# icm.net
KiCad netlist of a schematic drawn in Altium Designer
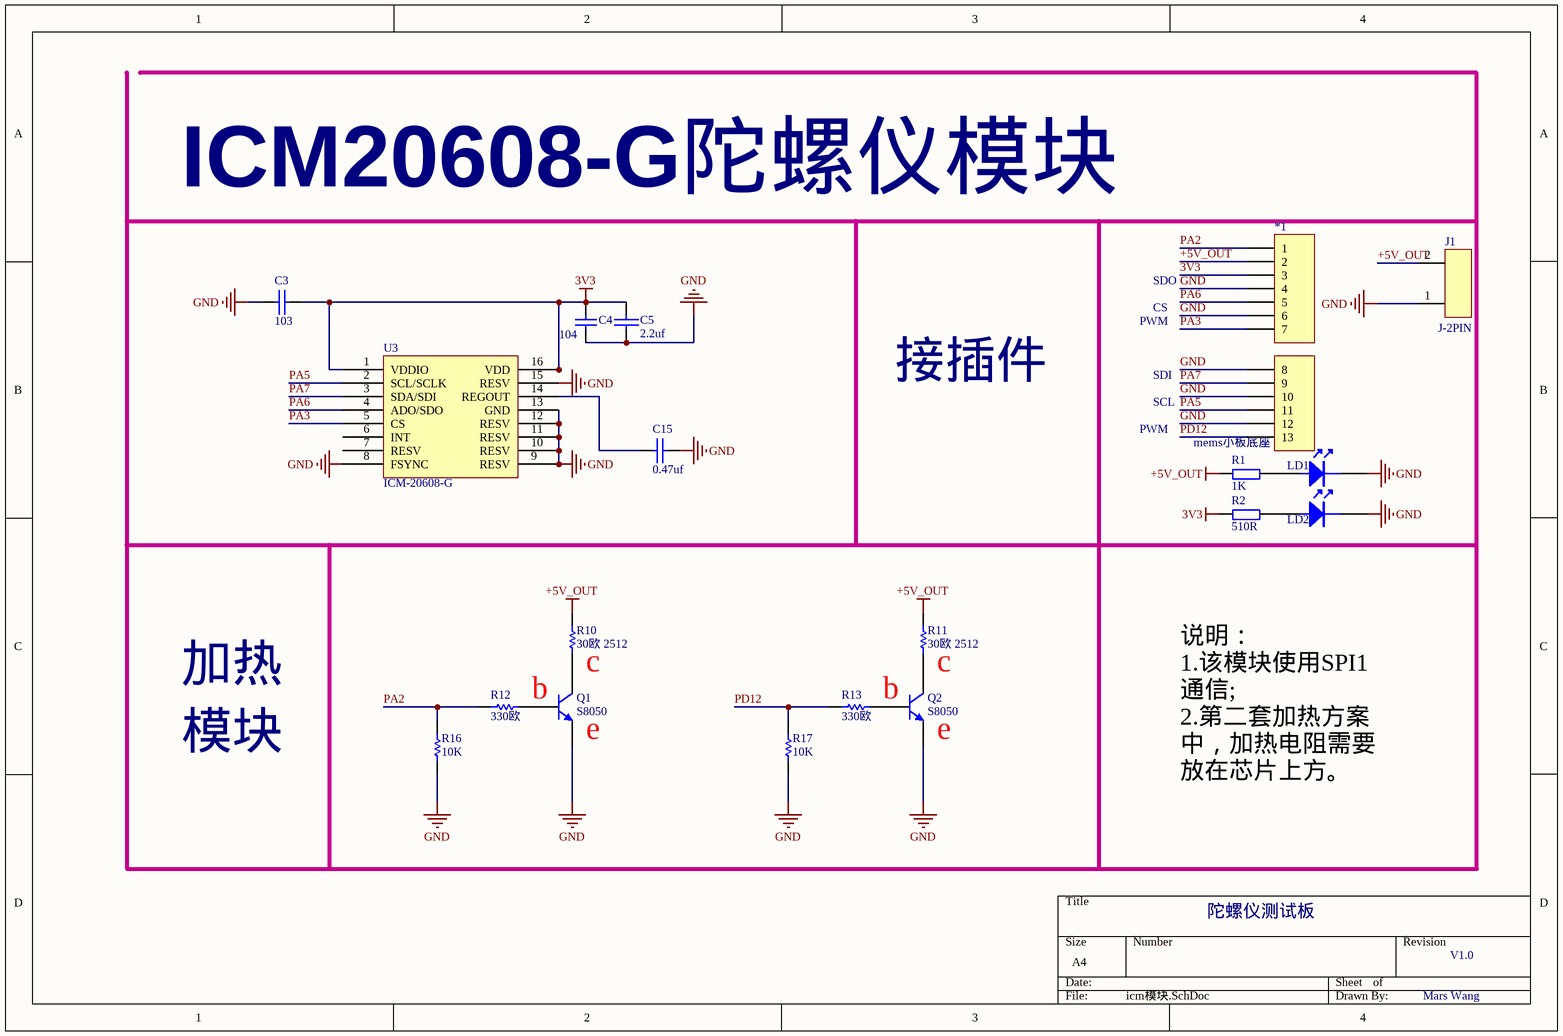
[diagram p0: icm模块.SchDoc]

(export (version "E")
  (design (tool "Eeschema 10.0.6"))
  (components
    (comp (ref "*1") (value "mems小板底座") (footprint "mems小板底座") (libsource (lib "ICM模块") (part "mems小板底座")))
    (comp (ref "C3")
      (value "103")
      (footprint "C-0805C")
      (description "Capacitor")
      (libsource (lib "ACTION原理图库") (part "C-贴片电容"))
    )
    (comp (ref "C4")
      (value "104")
      (footprint "C-0805C")
      (description "Capacitor")
      (fields (field (name "PUBLISHER") "Altium Limited"))
      (libsource (lib "Miscellaneous Devices") (part "C-贴片电容"))
    )
    (comp (ref "C5")
      (value "2.2uf")
      (footprint "C-0805C")
      (description "Capacitor")
      (libsource (lib "ACTION原理图库") (part "C-贴片电容"))
    )
    (comp (ref "C15")
      (value "0.47uf")
      (footprint "C-0805C")
      (description "Capacitor")
      (libsource (lib "ACTION原理图库") (part "C-贴片电容"))
    )
    (comp (ref "J1")
      (value "J-2PIN")
      (footprint "J-2-2.54-xh")
      (description "SOCKET")
      (libsource (lib "ACTION原理图库") (part "J-2PIN"))
    )
    (comp (ref "LD1") (value "~") (footprint "D-0603D") (libsource (lib "ACTION原理图库") (part "LED")))
    (comp (ref "LD2") (value "~") (footprint "D-0603D") (libsource (lib "ACTION原理图库") (part "LED")))
    (comp (ref "Q1")
      (value "S8050")
      (footprint "SOT-233-3")
      (description "NPN Bipolar Transistor")
      (fields (field (name "PUBLISHER") "Altium Limited"))
      (libsource (lib "Miscellaneous Devices") (part "NPN"))
    )
    (comp (ref "Q2")
      (value "S8050")
      (footprint "SOT-233-3")
      (description "NPN Bipolar Transistor")
      (fields (field (name "PUBLISHER") "Altium Limited"))
      (libsource (lib "Miscellaneous Devices") (part "NPN"))
    )
    (comp (ref "R1")
      (value "1K")
      (footprint "R-0603R")
      (description "RES, 10K, 5%, 0.1 W, 0603")
      (libsource (lib "ACTION原理图库") (part "Resistor"))
    )
    (comp (ref "R2")
      (value "510R")
      (footprint "R-0603R")
      (description "RES, 10K, 5%, 0.1 W, 0603")
      (libsource (lib "ACTION原理图库") (part "Resistor"))
    )
    (comp (ref "R10")
      (value "30欧 2512")
      (footprint "R-3925R（锰铜）")
      (description "Semiconductor Resistor")
      (fields (field (name "PUBLISHER") "Altium Limited"))
      (libsource (lib "大赛无线手柄") (part "Res Semi"))
    )
    (comp (ref "R11")
      (value "30欧 2512")
      (footprint "PCBComponent_1")
      (description "Semiconductor Resistor")
      (fields (field (name "PUBLISHER") "Altium Limited"))
      (libsource (lib "大赛无线手柄") (part "Res Semi"))
    )
    (comp (ref "R12")
      (value "330欧")
      (footprint "R-0603R")
      (description "Semiconductor Resistor")
      (fields (field (name "PUBLISHER") "Altium Limited"))
      (libsource (lib "altium-import") (part "root_0_Res Semi_"))
    )
    (comp (ref "R13")
      (value "330欧")
      (footprint "R-0603R")
      (description "Semiconductor Resistor")
      (fields (field (name "PUBLISHER") "Altium Limited"))
      (libsource (lib "altium-import") (part "root_0_Res Semi_"))
    )
    (comp (ref "R16")
      (value "10K")
      (footprint "R-0603R")
      (description "Semiconductor Resistor")
      (fields (field (name "PUBLISHER") "Altium Limited"))
      (libsource (lib "大赛无线手柄") (part "Res Semi"))
    )
    (comp (ref "R17")
      (value "10K")
      (footprint "R-0603R")
      (description "Semiconductor Resistor")
      (fields (field (name "PUBLISHER") "Altium Limited"))
      (libsource (lib "大赛无线手柄") (part "Res Semi"))
    )
    (comp (ref "U3")
      (value "ICM-20608-G")
      (footprint "ICM20608-G")
      (libsource (lib "ACTION原理图库") (part "ICM-20608-G"))
    )
  )
  (nets
    (net (code "1") (name "+5V_OUT") (class "Default")
      (node (ref "*1") (pin "2") (pinfunction "2_2") (pintype "passive"))
      (node (ref "J1") (pin "2") (pinfunction "2_2") (pintype "passive"))
      (node (ref "R1") (pin "1") (pintype "passive"))
      (node (ref "R10") (pin "2") (pinfunction "2_2") (pintype "passive"))
      (node (ref "R11") (pin "2") (pinfunction "2_2") (pintype "passive"))
    )
    (net (code "2") (name "/PA2") (class "Default")
      (node (ref "*1") (pin "1") (pinfunction "1_1") (pintype "passive"))
      (node (ref "R12") (pin "1") (pinfunction "1_1") (pintype "passive"))
      (node (ref "R16") (pin "2") (pinfunction "2_2") (pintype "passive"))
    )
    (net (code "3") (name "/PA3") (class "Default")
      (node (ref "*1") (pin "7") (pinfunction "7_7") (pintype "passive"))
      (node (ref "U3") (pin "5") (pinfunction "CS_5") (pintype "passive"))
    )
    (net (code "4") (name "/PA5") (class "Default")
      (node (ref "*1") (pin "11") (pinfunction "11_11") (pintype "passive"))
      (node (ref "U3") (pin "2") (pinfunction "SCL/SCLK_2") (pintype "passive"))
    )
    (net (code "5") (name "/PA6") (class "Default")
      (node (ref "*1") (pin "5") (pinfunction "5_5") (pintype "passive"))
      (node (ref "U3") (pin "4") (pinfunction "ADO/SDO_4") (pintype "passive"))
    )
    (net (code "6") (name "/PA7") (class "Default")
      (node (ref "*1") (pin "9") (pinfunction "9_9") (pintype "passive"))
      (node (ref "U3") (pin "3") (pinfunction "SDA/SDI_3") (pintype "passive"))
    )
    (net (code "7") (name "/PD12") (class "Default")
      (node (ref "*1") (pin "13") (pinfunction "13_13") (pintype "passive"))
      (node (ref "R13") (pin "1") (pinfunction "1_1") (pintype "passive"))
      (node (ref "R17") (pin "2") (pinfunction "2_2") (pintype "passive"))
    )
    (net (code "8") (name "3V3") (class "Default")
      (node (ref "*1") (pin "3") (pinfunction "3_3") (pintype "passive"))
      (node (ref "C3") (pin "1") (pinfunction "1_1") (pintype "passive"))
      (node (ref "C4") (pin "1") (pinfunction "1_1") (pintype "passive"))
      (node (ref "C5") (pin "2") (pinfunction "2_2") (pintype "passive"))
      (node (ref "R2") (pin "1") (pintype "passive"))
      (node (ref "U3") (pin "1") (pinfunction "VDDIO_1") (pintype "passive"))
      (node (ref "U3") (pin "16") (pinfunction "VDD_16") (pintype "passive"))
    )
    (net (code "9") (name "GND") (class "Default")
      (node (ref "*1") (pin "10") (pinfunction "10_10") (pintype "passive"))
      (node (ref "*1") (pin "12") (pinfunction "12_12") (pintype "passive"))
      (node (ref "*1") (pin "4") (pinfunction "4_4") (pintype "passive"))
      (node (ref "*1") (pin "6") (pinfunction "6_6") (pintype "passive"))
      (node (ref "*1") (pin "8") (pinfunction "8_8") (pintype "passive"))
      (node (ref "C15") (pin "1") (pinfunction "1_1") (pintype "passive"))
      (node (ref "C3") (pin "2") (pinfunction "2_2") (pintype "passive"))
      (node (ref "C4") (pin "2") (pinfunction "2_2") (pintype "passive"))
      (node (ref "C5") (pin "1") (pinfunction "1_1") (pintype "passive"))
      (node (ref "J1") (pin "1") (pinfunction "1_1") (pintype "passive"))
      (node (ref "LD1") (pin "2") (pinfunction "2_2") (pintype "passive"))
      (node (ref "LD2") (pin "2") (pinfunction "2_2") (pintype "passive"))
      (node (ref "Q1") (pin "3") (pinfunction "E_3") (pintype "passive"))
      (node (ref "Q2") (pin "3") (pinfunction "E_3") (pintype "passive"))
      (node (ref "R16") (pin "1") (pinfunction "1_1") (pintype "passive"))
      (node (ref "R17") (pin "1") (pinfunction "1_1") (pintype "passive"))
      (node (ref "U3") (pin "10") (pinfunction "RESV_10") (pintype "passive"))
      (node (ref "U3") (pin "11") (pinfunction "RESV_11") (pintype "passive"))
      (node (ref "U3") (pin "12") (pinfunction "RESV_12") (pintype "passive"))
      (node (ref "U3") (pin "13") (pinfunction "GND_13") (pintype "passive"))
      (node (ref "U3") (pin "15") (pinfunction "RESV_15") (pintype "passive"))
      (node (ref "U3") (pin "8") (pinfunction "FSYNC_8") (pintype "passive"))
      (node (ref "U3") (pin "9") (pinfunction "RESV_9") (pintype "passive"))
    )
    (net (code "10") (name "Net-(LD1-Pad1)") (class "Default")
      (node (ref "LD1") (pin "1") (pinfunction "1_1") (pintype "passive"))
      (node (ref "R1") (pin "2") (pintype "passive"))
    )
    (net (code "11") (name "Net-(LD2-Pad1)") (class "Default")
      (node (ref "LD2") (pin "1") (pinfunction "1_1") (pintype "passive"))
      (node (ref "R2") (pin "2") (pintype "passive"))
    )
    (net (code "12") (name "Net-(Q1-B)") (class "Default")
      (node (ref "Q1") (pin "2") (pinfunction "B_2") (pintype "passive"))
      (node (ref "R12") (pin "2") (pinfunction "2_2") (pintype "passive"))
    )
    (net (code "13") (name "Net-(Q1-C)") (class "Default")
      (node (ref "Q1") (pin "1") (pinfunction "C_1") (pintype "passive"))
      (node (ref "R10") (pin "1") (pinfunction "1_1") (pintype "passive"))
    )
    (net (code "14") (name "Net-(Q2-B)") (class "Default")
      (node (ref "Q2") (pin "2") (pinfunction "B_2") (pintype "passive"))
      (node (ref "R13") (pin "2") (pinfunction "2_2") (pintype "passive"))
    )
    (net (code "15") (name "Net-(Q2-C)") (class "Default")
      (node (ref "Q2") (pin "1") (pinfunction "C_1") (pintype "passive"))
      (node (ref "R11") (pin "1") (pinfunction "1_1") (pintype "passive"))
    )
    (net (code "16") (name "Net-(U3-REGOUT)") (class "Default")
      (node (ref "C15") (pin "2") (pinfunction "2_2") (pintype "passive"))
      (node (ref "U3") (pin "14") (pinfunction "REGOUT_14") (pintype "passive"))
    )
    (net (code "17") (name "unconnected-(U3-INT-Pad6)") (class "Default")
      (node (ref "U3") (pin "6") (pinfunction "INT_6") (pintype "passive"))
    )
    (net (code "18") (name "unconnected-(U3-RESV-Pad7)") (class "Default")
      (node (ref "U3") (pin "7") (pinfunction "RESV_7") (pintype "passive"))
    )
  )
)
